# RF_Ticketing_Slave.net
KiCad netlist of a schematic drawn in Altium Designer
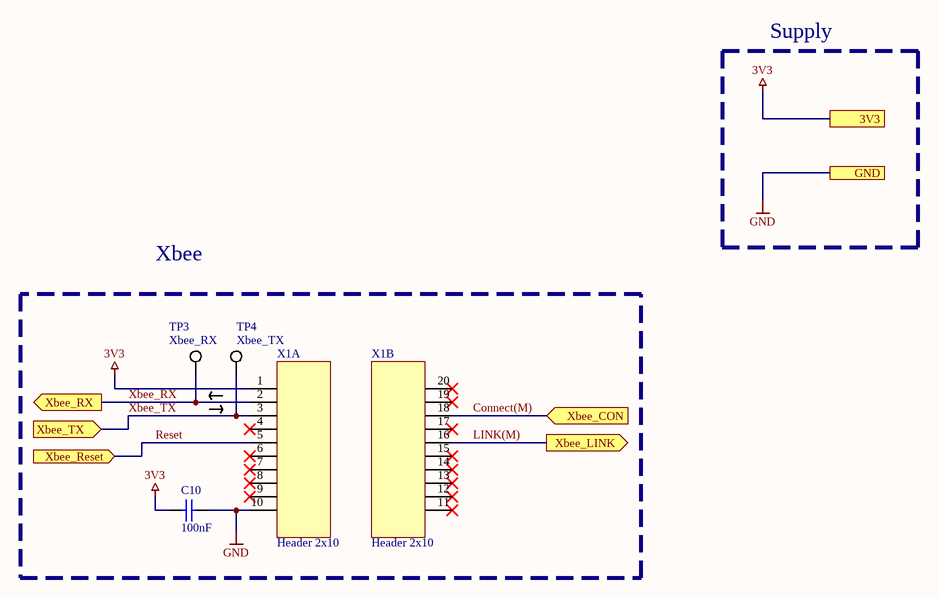
[diagram p0: RF_Ticketing_Slave.SchDoc]

(export (version "E")
  (design (tool "Eeschema 10.0.6"))
  (components
    (comp (ref "C10")
      (value "100nF")
      (footprint "6-0805_N")
      (description "Capacitor")
      (libsource (lib "Miscellaneous Devices") (part "Cap"))
    )
    (comp (ref "TP3")
      (value "Xbee_RX")
      (footprint "KSTN-5019_V")
      (description "Test Point, 1 Position SMD, RoHS, Tape and Reel")
      (libsource (lib "Altium Content Vault") (part "TESTPOINT_WHITE"))
    )
    (comp (ref "TP4")
      (value "Xbee_TX")
      (footprint "KSTN-5019_V")
      (description "Test Point, 1 Position SMD, RoHS, Tape and Reel")
      (libsource (lib "Altium Content Vault") (part "TESTPOINT_WHITE"))
    )
    (comp (ref "X1")
      (value "Header 2x10")
      (footprint "ZB-SB")
      (description "Header 2x10\r\nXbee de letml(1623) ou xbee XB24CAUIT-001")
      (libsource (lib "PCB_Ticketing_Slave") (part "HDR ZB-SB 2x10_1"))
    )
  )
  (nets
    (net (code "1") (name "/Connect(M)") (class "Default") (node (ref "X1") (pin "18") (pintype "passive")))
    (net (code "2") (name "/LINK(M)") (class "Default") (node (ref "X1") (pin "16") (pintype "passive")))
    (net (code "3") (name "/Reset") (class "Default") (node (ref "X1") (pin "5") (pintype "passive")))
    (net (code "4") (name "/Xbee_RX") (class "Default")
      (node (ref "TP3") (pin "1") (pinfunction "1_1") (pintype "passive"))
      (node (ref "X1") (pin "2") (pintype "passive"))
    )
    (net (code "5") (name "/Xbee_TX") (class "Default")
      (node (ref "TP4") (pin "1") (pinfunction "1_1") (pintype "passive"))
      (node (ref "X1") (pin "3") (pintype "passive"))
    )
    (net (code "6") (name "3V3") (class "Default")
      (node (ref "C10") (pin "2") (pinfunction "2_2") (pintype "passive"))
      (node (ref "X1") (pin "1") (pintype "passive"))
    )
    (net (code "7") (name "GND") (class "Default")
      (node (ref "C10") (pin "1") (pinfunction "1_1") (pintype "passive"))
      (node (ref "X1") (pin "10") (pintype "passive"))
    )
    (net (code "8") (name "unconnected-(X1-Pad4)") (class "Default")
      (node (ref "X1") (pin "4") (pintype "passive+no_connect"))
    )
    (net (code "9") (name "unconnected-(X1-Pad6)") (class "Default")
      (node (ref "X1") (pin "6") (pintype "passive+no_connect"))
    )
    (net (code "10") (name "unconnected-(X1-Pad7)") (class "Default")
      (node (ref "X1") (pin "7") (pintype "passive+no_connect"))
    )
    (net (code "11") (name "unconnected-(X1-Pad8)") (class "Default")
      (node (ref "X1") (pin "8") (pintype "passive+no_connect"))
    )
    (net (code "12") (name "unconnected-(X1-Pad9)") (class "Default")
      (node (ref "X1") (pin "9") (pintype "passive+no_connect"))
    )
    (net (code "13") (name "unconnected-(X1-Pad11)") (class "Default")
      (node (ref "X1") (pin "11") (pintype "passive+no_connect"))
    )
    (net (code "14") (name "unconnected-(X1-Pad12)") (class "Default")
      (node (ref "X1") (pin "12") (pintype "passive+no_connect"))
    )
    (net (code "15") (name "unconnected-(X1-Pad13)") (class "Default")
      (node (ref "X1") (pin "13") (pintype "passive+no_connect"))
    )
    (net (code "16") (name "unconnected-(X1-Pad14)") (class "Default")
      (node (ref "X1") (pin "14") (pintype "passive+no_connect"))
    )
    (net (code "17") (name "unconnected-(X1-Pad15)") (class "Default")
      (node (ref "X1") (pin "15") (pintype "passive+no_connect"))
    )
    (net (code "18") (name "unconnected-(X1-Pad17)") (class "Default")
      (node (ref "X1") (pin "17") (pintype "passive+no_connect"))
    )
    (net (code "19") (name "unconnected-(X1-Pad19)") (class "Default")
      (node (ref "X1") (pin "19") (pintype "passive+no_connect"))
    )
    (net (code "20") (name "unconnected-(X1-Pad20)") (class "Default")
      (node (ref "X1") (pin "20") (pintype "passive+no_connect"))
    )
  )
)
